# sar19-coral-connector.net
KiCad netlist of a schematic drawn in Altium Designer
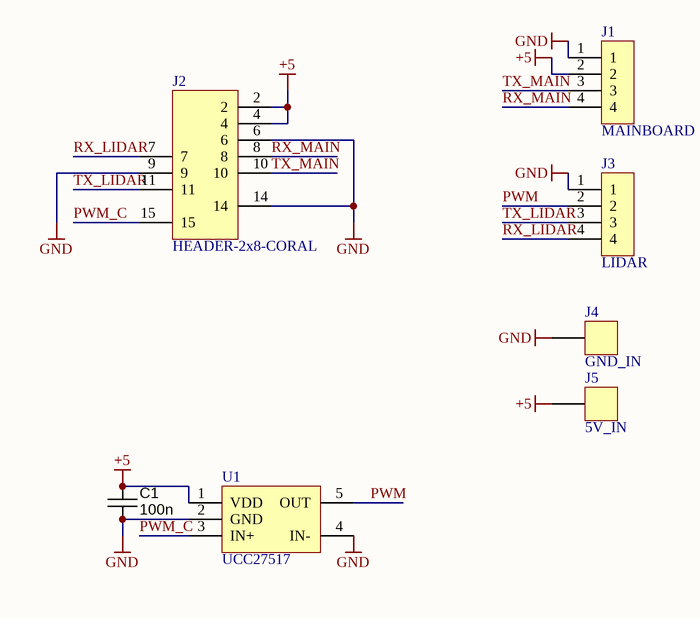
[diagram p0: sar19-coral-connector.SchDoc]

(export (version "E")
  (design (tool "Eeschema 10.0.6"))
  (components
    (comp (ref "C1")
      (value "100n")
      (footprint "CAPC1608X90N")
      (description "Capacitor SMD Cer 100nF 10% 50V X7R 0603")
      (fields (field (name "TOLERANCE") "±10%"))
      (libsource (lib "PBL - Capacitors") (part "CAPC_100n_0603_X7R_50V_10%"))
    )
    (comp (ref "J1")
      (value "MAINBOARD")
      (footprint "MICRO-MATCH-FOB-SIDE-04")
      (libsource (lib "connectors_micromatch") (part "HEADER-4"))
    )
    (comp (ref "J2")
      (value "HEADER-2x8-CORAL")
      (footprint "PIN-HEADER-2x8-CORAL")
      (libsource (lib "sar19-coral-connector") (part "HEADER-2x8-CORAL"))
    )
    (comp (ref "J3")
      (value "LIDAR")
      (footprint "MICRO-MATCH-FOB-SIDE-04")
      (libsource (lib "connectors_micromatch") (part "HEADER-4"))
    )
    (comp (ref "J4")
      (value "GND_IN")
      (footprint "POWER-PAD-4x3")
      (libsource (lib "connectors") (part "HEADER-1"))
    )
    (comp (ref "J5")
      (value "5V_IN")
      (footprint "POWER-PAD-4x3")
      (libsource (lib "connectors") (part "HEADER-1"))
    )
    (comp (ref "U1")
      (value "UCC27517")
      (footprint "SOT23-5")
      (libsource (lib "sar19-coral-connector") (part "UCC27517"))
    )
  )
  (nets
    (net (code "1") (name "+5") (class "Default")
      (node (ref "C1") (pin "1") (pintype "passive"))
      (node (ref "J1") (pin "2") (pinfunction "2_2") (pintype "passive"))
      (node (ref "J2") (pin "2") (pinfunction "2_2") (pintype "passive"))
      (node (ref "J2") (pin "4") (pinfunction "4_4") (pintype "passive"))
      (node (ref "J5") (pin "1") (pinfunction "1_1") (pintype "passive"))
      (node (ref "U1") (pin "1") (pinfunction "VDD_1") (pintype "passive"))
    )
    (net (code "2") (name "/PWM") (class "Default")
      (node (ref "J3") (pin "2") (pinfunction "2_2") (pintype "passive"))
      (node (ref "U1") (pin "5") (pinfunction "OUT_5") (pintype "passive"))
    )
    (net (code "3") (name "/PWM_C") (class "Default")
      (node (ref "J2") (pin "15") (pinfunction "15_15") (pintype "passive"))
      (node (ref "U1") (pin "3") (pinfunction "IN+_3") (pintype "passive"))
    )
    (net (code "4") (name "/RX_LIDAR") (class "Default")
      (node (ref "J2") (pin "7") (pinfunction "7_7") (pintype "passive"))
      (node (ref "J3") (pin "4") (pinfunction "4_4") (pintype "passive"))
    )
    (net (code "5") (name "/RX_MAIN") (class "Default")
      (node (ref "J1") (pin "4") (pinfunction "4_4") (pintype "passive"))
      (node (ref "J2") (pin "8") (pinfunction "8_8") (pintype "passive"))
    )
    (net (code "6") (name "/TX_LIDAR") (class "Default")
      (node (ref "J2") (pin "11") (pinfunction "11_11") (pintype "passive"))
      (node (ref "J3") (pin "3") (pinfunction "3_3") (pintype "passive"))
    )
    (net (code "7") (name "/TX_MAIN") (class "Default")
      (node (ref "J1") (pin "3") (pinfunction "3_3") (pintype "passive"))
      (node (ref "J2") (pin "10") (pinfunction "10_10") (pintype "passive"))
    )
    (net (code "8") (name "GND") (class "Default")
      (node (ref "C1") (pin "2") (pintype "passive"))
      (node (ref "J1") (pin "1") (pinfunction "1_1") (pintype "passive"))
      (node (ref "J2") (pin "14") (pinfunction "14_14") (pintype "passive"))
      (node (ref "J2") (pin "6") (pinfunction "6_6") (pintype "passive"))
      (node (ref "J2") (pin "9") (pinfunction "9_9") (pintype "passive"))
      (node (ref "J3") (pin "1") (pinfunction "1_1") (pintype "passive"))
      (node (ref "J4") (pin "1") (pinfunction "1_1") (pintype "passive"))
      (node (ref "U1") (pin "2") (pinfunction "GND_2") (pintype "passive"))
      (node (ref "U1") (pin "4") (pinfunction "IN-_4") (pintype "passive"))
    )
  )
)
